# Sheet1.net
KiCad netlist of a schematic drawn in Altium Designer
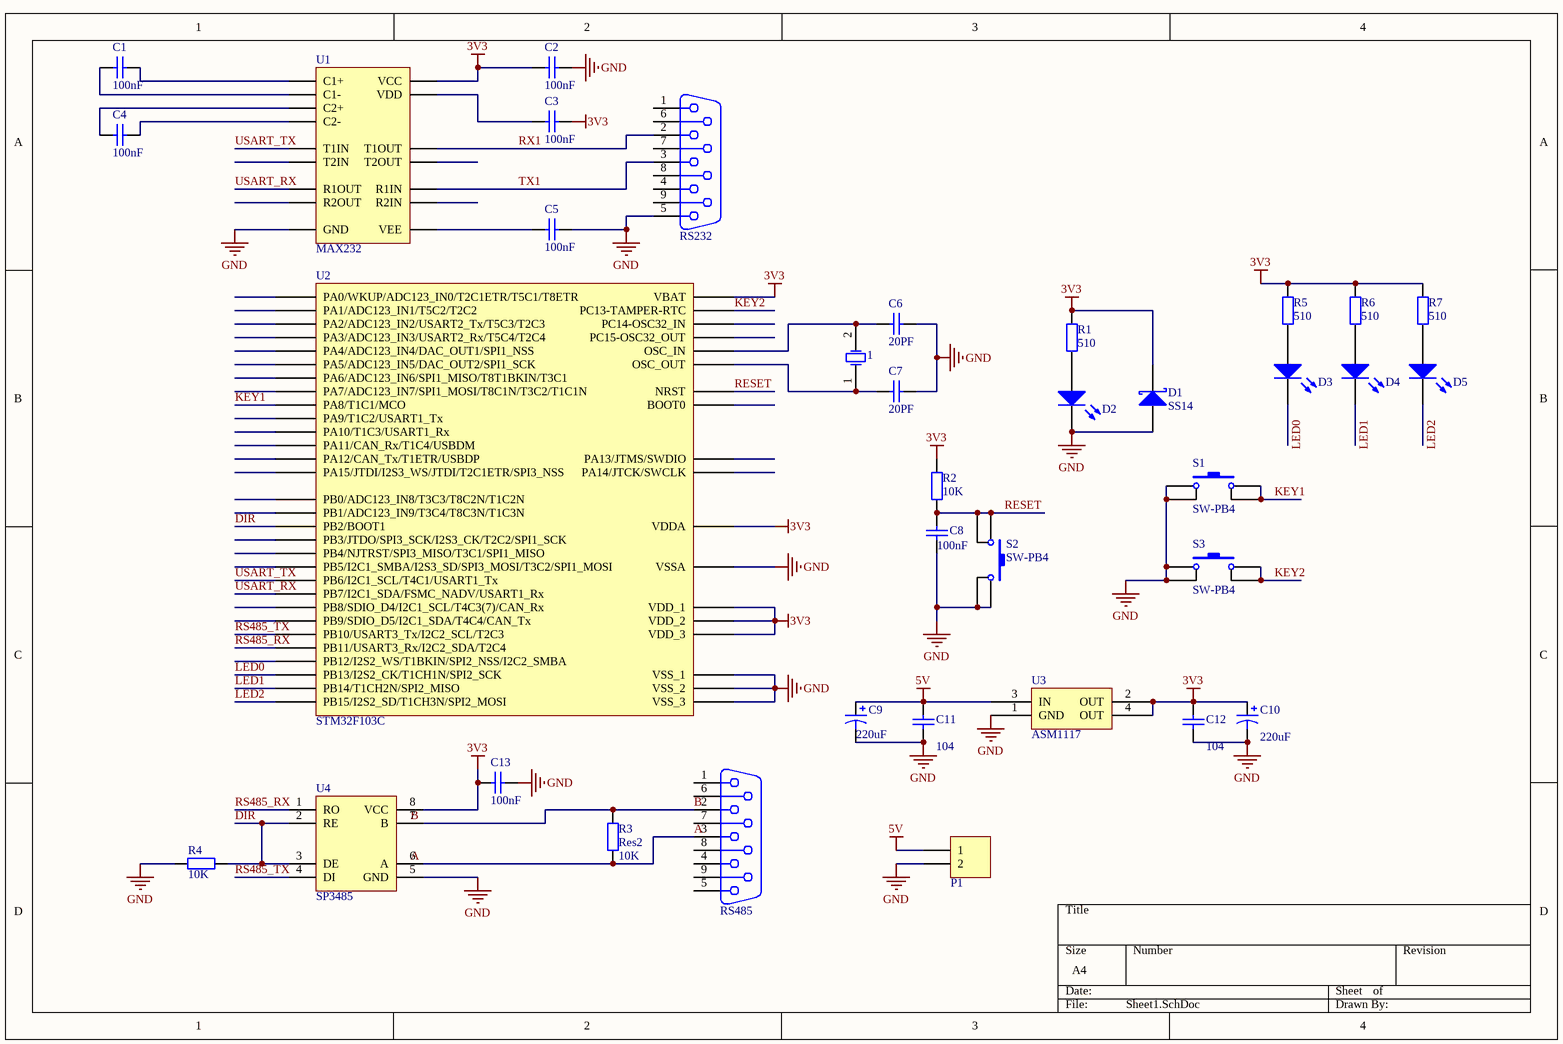
[diagram p0: Sheet1.SchDoc]

(export (version "E")
  (design (tool "Eeschema 10.0.6"))
  (components
    (comp (ref "1")
      (value "XTAL")
      (footprint "XTAL")
      (description "Crystal Oscillator")
      (fields (field (name "PUBLISHER") "Altium Limited"))
      (libsource (lib "Miscellaneous Devices") (part "XTAL"))
    )
    (comp (ref "C1")
      (value "100nF")
      (footprint "0805")
      (description "Capacitor")
      (fields (field (name "Comment") "Cap") (field (name "PUBLISHER") "Altium Limited"))
      (libsource (lib "Miscellaneous Devices") (part "Cap"))
    )
    (comp (ref "C2")
      (value "100nF")
      (footprint "0805")
      (description "Capacitor")
      (fields (field (name "Comment") "Cap") (field (name "PUBLISHER") "Altium Limited"))
      (libsource (lib "Miscellaneous Devices") (part "Cap"))
    )
    (comp (ref "C3")
      (value "100nF")
      (footprint "0805")
      (description "Capacitor")
      (fields (field (name "Comment") "Cap") (field (name "PUBLISHER") "Altium Limited"))
      (libsource (lib "Miscellaneous Devices") (part "Cap"))
    )
    (comp (ref "C4")
      (value "100nF")
      (footprint "0805")
      (description "Capacitor")
      (fields (field (name "Comment") "Cap") (field (name "PUBLISHER") "Altium Limited"))
      (libsource (lib "Miscellaneous Devices") (part "Cap"))
    )
    (comp (ref "C5")
      (value "100nF")
      (footprint "0805")
      (description "Capacitor")
      (fields (field (name "Comment") "Cap") (field (name "PUBLISHER") "Altium Limited"))
      (libsource (lib "Miscellaneous Devices") (part "Cap"))
    )
    (comp (ref "C6")
      (value "20PF")
      (footprint "0805")
      (description "Capacitor")
      (fields (field (name "PUBLISHER") "Altium Limited"))
      (libsource (lib "Miscellaneous Devices") (part "Cap"))
    )
    (comp (ref "C7")
      (value "20PF")
      (footprint "0805")
      (description "Capacitor")
      (fields (field (name "PUBLISHER") "Altium Limited"))
      (libsource (lib "Miscellaneous Devices") (part "Cap"))
    )
    (comp (ref "C8")
      (value "100nF")
      (footprint "0805")
      (description "Capacitor")
      (fields (field (name "Comment") "Cap") (field (name "PUBLISHER") "Altium Limited"))
      (libsource (lib "Miscellaneous Devices") (part "Cap"))
    )
    (comp (ref "C9")
      (value "220uF")
      (footprint "CAP-3528")
      (description "Polarized Capacitor (Radial)")
      (fields (field (name "Comment") "Cap Pol1") (field (name "PUBLISHER") "Altium Limited"))
      (libsource (lib "Miscellaneous Devices") (part "Cap Pol1"))
    )
    (comp (ref "C10")
      (value "220uF")
      (footprint "CAP-3528")
      (description "Polarized Capacitor (Radial)")
      (fields (field (name "Comment") "Cap Pol1") (field (name "PUBLISHER") "Altium Limited"))
      (libsource (lib "Miscellaneous Devices") (part "Cap Pol1"))
    )
    (comp (ref "C11")
      (value "104")
      (footprint "0805")
      (description "Capacitor")
      (fields (field (name "Comment") "Cap") (field (name "PUBLISHER") "Altium Limited"))
      (libsource (lib "Miscellaneous Devices") (part "Cap"))
    )
    (comp (ref "C12")
      (value "104")
      (footprint "0805")
      (description "Capacitor")
      (fields (field (name "Comment") "Cap") (field (name "PUBLISHER") "Altium Limited"))
      (libsource (lib "Miscellaneous Devices") (part "Cap"))
    )
    (comp (ref "C13")
      (value "100nF")
      (footprint "0805")
      (description "Capacitor")
      (fields (field (name "Comment") "Cap") (field (name "PUBLISHER") "Altium Limited"))
      (libsource (lib "Miscellaneous Devices") (part "Cap"))
    )
    (comp (ref "D1")
      (value "D-Schottky")
      (footprint "DIODE-SMA")
      (description "肖特基二极管")
      (fields (field (name "TYPE") "SS14") (field (name "PUBLISHER") "Altium Limited"))
      (libsource (lib "Fszhang") (part "D-Schottky"))
    )
    (comp (ref "D2")
      (value "LED0")
      (footprint "LED_0805")
      (description "发光二极管")
      (fields (field (name "PUBLISHER") "Altium Limited"))
      (libsource (lib "Fszhang") (part "LED0"))
    )
    (comp (ref "D3")
      (value "LED0")
      (footprint "LED_0805")
      (description "发光二极管")
      (fields (field (name "PUBLISHER") "Altium Limited"))
      (libsource (lib "Fszhang") (part "LED0"))
    )
    (comp (ref "D4")
      (value "LED0")
      (footprint "LED_0805")
      (description "发光二极管")
      (fields (field (name "PUBLISHER") "Altium Limited"))
      (libsource (lib "Fszhang") (part "LED0"))
    )
    (comp (ref "D5")
      (value "LED0")
      (footprint "LED_0805")
      (description "发光二极管")
      (fields (field (name "PUBLISHER") "Altium Limited"))
      (libsource (lib "Fszhang") (part "LED0"))
    )
    (comp (ref "P1")
      (value "Header 2")
      (footprint "HDR2X1_D1")
      (description "接插件")
      (fields (field (name "PUBLISHER") "Altium Limited"))
      (libsource (lib "Fszhang") (part "Header 2"))
    )
    (comp (ref "R1")
      (value "510")
      (footprint "0805")
      (description "Resistor")
      (fields (field (name "PUBLISHER") "Altium Limited"))
      (libsource (lib "") (part "Res2_1"))
    )
    (comp (ref "R2")
      (value "10K")
      (footprint "0805")
      (description "Resistor")
      (fields (field (name "PUBLISHER") "Altium Limited"))
      (libsource (lib "") (part "Res2_1"))
    )
    (comp (ref "R3")
      (value "Res2")
      (footprint "0805")
      (description "Resistor")
      (fields (field (name "ALTIUM_VALUE") "10K") (field (name "PUBLISHER") "Altium Limited"))
      (libsource (lib "") (part "Res2_2"))
    )
    (comp (ref "R4")
      (value "10K")
      (footprint "0805")
      (description "Resistor")
      (fields (field (name "PUBLISHER") "Altium Limited"))
      (libsource (lib "Miscellaneous Devices") (part "Res2"))
    )
    (comp (ref "R5")
      (value "510")
      (footprint "0805")
      (description "Resistor")
      (fields (field (name "PUBLISHER") "Altium Limited"))
      (libsource (lib "") (part "Res2_1"))
    )
    (comp (ref "R6")
      (value "510")
      (footprint "0805")
      (description "Resistor")
      (fields (field (name "PUBLISHER") "Altium Limited"))
      (libsource (lib "") (part "Res2_1"))
    )
    (comp (ref "R7")
      (value "510")
      (footprint "0805")
      (description "Resistor")
      (fields (field (name "PUBLISHER") "Altium Limited"))
      (libsource (lib "") (part "Res2_1"))
    )
    (comp (ref "RS232")
      (value "D Connector 9")
      (footprint "HDR3X1_D1")
      (description "串口")
      (fields (field (name "PUBLISHER") "Altium Limited"))
      (libsource (lib "Fszhang") (part "D Connector 9"))
    )
    (comp (ref "RS485")
      (value "D Connector 9")
      (footprint "HDR2X1_D1")
      (description "串口")
      (fields (field (name "PUBLISHER") "Altium Limited"))
      (libsource (lib "Fszhang") (part "D Connector 9"))
    )
    (comp (ref "S1")
      (value "SW-PB4")
      (footprint "SW_PB4_A1")
      (description "微动开关")
      (fields (field (name "PUBLISHER") "Altium Limited"))
      (libsource (lib "Fszhang") (part "SW-PB4"))
    )
    (comp (ref "S2")
      (value "SW-PB4")
      (footprint "SW_PB4_A1")
      (description "微动开关")
      (fields (field (name "PUBLISHER") "Altium Limited"))
      (libsource (lib "Fszhang") (part "SW-PB4"))
    )
    (comp (ref "S3")
      (value "SW-PB4")
      (footprint "SW_PB4_A1")
      (description "微动开关")
      (fields (field (name "PUBLISHER") "Altium Limited"))
      (libsource (lib "Fszhang") (part "SW-PB4"))
    )
    (comp (ref "U1")
      (value "MAX232")
      (footprint "NSO16_M")
      (description "+5V Powered, Multi-Channel RS-232 Driver/Receiver")
      (fields (field (name "PUBLISHER") "Altium Limited"))
      (libsource (lib "Fszhang") (part "MAX232"))
    )
    (comp (ref "U2")
      (value "STM32F103C")
      (footprint "LQFP-48_M")
      (description "STM32单片机48引脚")
      (libsource (lib "Fszhang") (part "STM32F103C"))
    )
    (comp (ref "U3")
      (value "ASM1117")
      (footprint "SOT-223")
      (description "3.3V稳压芯片")
      (libsource (lib "Fszhang") (part "ASM1117"))
    )
    (comp (ref "U4")
      (value "SP3485")
      (footprint "NSO8_N")
      (description "485总线芯片")
      (libsource (lib "Fszhang") (part "SP3485"))
    )
  )
  (nets
    (net (code "1") (name "/A") (class "Default")
      (node (ref "R3") (pin "2") (pinfunction "2_2") (pintype "passive"))
      (node (ref "RS485") (pin "3") (pinfunction "3_3") (pintype "passive"))
      (node (ref "U4") (pin "6") (pinfunction "A_6") (pintype "passive"))
    )
    (net (code "2") (name "/B") (class "Default")
      (node (ref "R3") (pin "1") (pinfunction "1_1") (pintype "passive"))
      (node (ref "RS485") (pin "2") (pinfunction "2_2") (pintype "passive"))
      (node (ref "U4") (pin "7") (pinfunction "B_7") (pintype "passive"))
    )
    (net (code "3") (name "/DIR") (class "Default")
      (node (ref "R4") (pin "2") (pinfunction "2_2") (pintype "passive"))
      (node (ref "U2") (pin "20") (pinfunction "PB2/BOOT1_20") (pintype "passive"))
      (node (ref "U4") (pin "2") (pinfunction "RE_2") (pintype "passive"))
      (node (ref "U4") (pin "3") (pinfunction "DE_3") (pintype "passive"))
    )
    (net (code "4") (name "/KEY1") (class "Default")
      (node (ref "S1") (pin "2") (pinfunction "2_2") (pintype "passive"))
      (node (ref "S1") (pin "3") (pinfunction "3_3") (pintype "passive"))
      (node (ref "U2") (pin "29") (pinfunction "PA8/T1C1/MCO_29") (pintype "passive"))
    )
    (net (code "5") (name "/KEY2") (class "Default")
      (node (ref "S3") (pin "2") (pinfunction "2_2") (pintype "passive"))
      (node (ref "S3") (pin "3") (pinfunction "3_3") (pintype "passive"))
      (node (ref "U2") (pin "2") (pinfunction "PC13-TAMPER-RTC_2") (pintype "passive"))
    )
    (net (code "6") (name "/LED0") (class "Default")
      (node (ref "D3") (pin "2") (pinfunction "K_2") (pintype "passive"))
      (node (ref "U2") (pin "26") (pinfunction "PB13/I2S2_CK/T1CH1N/SPI2_SCK_26") (pintype "passive"))
    )
    (net (code "7") (name "/LED1") (class "Default")
      (node (ref "D4") (pin "2") (pinfunction "K_2") (pintype "passive"))
      (node (ref "U2") (pin "27") (pinfunction "PB14/T1CH2N/SPI2_MISO_27") (pintype "passive"))
    )
    (net (code "8") (name "/LED2") (class "Default")
      (node (ref "D5") (pin "2") (pinfunction "K_2") (pintype "passive"))
      (node (ref "U2") (pin "28") (pinfunction "PB15/I2S2_SD/T1CH3N/SPI2_MOSI_28") (pintype "passive"))
    )
    (net (code "9") (name "/RESET") (class "Default")
      (node (ref "C8") (pin "1") (pinfunction "1_1") (pintype "passive"))
      (node (ref "R2") (pin "1") (pinfunction "1_1") (pintype "passive"))
      (node (ref "S2") (pin "1") (pinfunction "1_1") (pintype "passive"))
      (node (ref "S2") (pin "4") (pinfunction "4_4") (pintype "passive"))
      (node (ref "U2") (pin "7") (pinfunction "NRST_7") (pintype "passive"))
    )
    (net (code "10") (name "/RS485_RX") (class "Default")
      (node (ref "U2") (pin "22") (pinfunction "PB11/USART3_Rx/I2C2_SDA/T2C4_22") (pintype "passive"))
      (node (ref "U4") (pin "1") (pinfunction "RO_1") (pintype "passive"))
    )
    (net (code "11") (name "/RS485_TX") (class "Default")
      (node (ref "U2") (pin "21") (pinfunction "PB10/USART3_Tx/I2C2_SCL/T2C3_21") (pintype "passive"))
      (node (ref "U4") (pin "4") (pinfunction "DI_4") (pintype "passive"))
    )
    (net (code "12") (name "/RX1") (class "Default")
      (node (ref "RS232") (pin "2") (pinfunction "2_2") (pintype "passive"))
      (node (ref "U1") (pin "14") (pinfunction "T1OUT_14") (pintype "passive"))
    )
    (net (code "13") (name "/TX1") (class "Default")
      (node (ref "RS232") (pin "3") (pinfunction "3_3") (pintype "passive"))
      (node (ref "U1") (pin "13") (pinfunction "R1IN_13") (pintype "passive"))
    )
    (net (code "14") (name "/USART_RX") (class "Default")
      (node (ref "U1") (pin "12") (pinfunction "R1OUT_12") (pintype "passive"))
      (node (ref "U2") (pin "43") (pinfunction "PB7/I2C1_SDA/FSMC_NADV/USART1_Rx_43") (pintype "passive"))
    )
    (net (code "15") (name "/USART_TX") (class "Default")
      (node (ref "U1") (pin "11") (pinfunction "T1IN_11") (pintype "passive"))
      (node (ref "U2") (pin "42") (pinfunction "PB6/I2C1_SCL/T4C1/USART1_Tx_42") (pintype "passive"))
    )
    (net (code "16") (name "3V3") (class "Default")
      (node (ref "C10") (pin "1") (pinfunction "1_1") (pintype "passive"))
      (node (ref "C12") (pin "2") (pinfunction "2_2") (pintype "passive"))
      (node (ref "C13") (pin "2") (pinfunction "2_2") (pintype "passive"))
      (node (ref "C2") (pin "1") (pinfunction "1_1") (pintype "passive"))
      (node (ref "C3") (pin "2") (pinfunction "2_2") (pintype "passive"))
      (node (ref "D1") (pin "2") (pinfunction "K_2") (pintype "passive"))
      (node (ref "R1") (pin "2") (pinfunction "2_2") (pintype "passive"))
      (node (ref "R2") (pin "2") (pinfunction "2_2") (pintype "passive"))
      (node (ref "R5") (pin "2") (pinfunction "2_2") (pintype "passive"))
      (node (ref "R6") (pin "2") (pinfunction "2_2") (pintype "passive"))
      (node (ref "R7") (pin "2") (pinfunction "2_2") (pintype "passive"))
      (node (ref "U1") (pin "16") (pinfunction "VCC_16") (pintype "power_in"))
      (node (ref "U2") (pin "1") (pinfunction "VBAT_1") (pintype "passive"))
      (node (ref "U2") (pin "24") (pinfunction "VDD_1_24") (pintype "passive"))
      (node (ref "U2") (pin "36") (pinfunction "VDD_2_36") (pintype "passive"))
      (node (ref "U2") (pin "48") (pinfunction "VDD_3_48") (pintype "passive"))
      (node (ref "U2") (pin "9") (pinfunction "VDDA_9") (pintype "passive"))
      (node (ref "U3") (pin "2") (pinfunction "OUT_2") (pintype "passive"))
      (node (ref "U3") (pin "4") (pinfunction "OUT_4") (pintype "passive"))
      (node (ref "U4") (pin "8") (pinfunction "VCC_8") (pintype "passive"))
    )
    (net (code "17") (name "5V") (class "Default")
      (node (ref "C11") (pin "2") (pinfunction "2_2") (pintype "passive"))
      (node (ref "C9") (pin "1") (pinfunction "1_1") (pintype "passive"))
      (node (ref "P1") (pin "1") (pinfunction "1_1") (pintype "passive"))
      (node (ref "U3") (pin "3") (pinfunction "IN_3") (pintype "passive"))
    )
    (net (code "18") (name "GND") (class "Default")
      (node (ref "C10") (pin "2") (pinfunction "2_2") (pintype "passive"))
      (node (ref "C11") (pin "1") (pinfunction "1_1") (pintype "passive"))
      (node (ref "C12") (pin "1") (pinfunction "1_1") (pintype "passive"))
      (node (ref "C13") (pin "1") (pinfunction "1_1") (pintype "passive"))
      (node (ref "C2") (pin "2") (pinfunction "2_2") (pintype "passive"))
      (node (ref "C5") (pin "2") (pinfunction "2_2") (pintype "passive"))
      (node (ref "C6") (pin "2") (pinfunction "2_2") (pintype "passive"))
      (node (ref "C7") (pin "2") (pinfunction "2_2") (pintype "passive"))
      (node (ref "C8") (pin "2") (pinfunction "2_2") (pintype "passive"))
      (node (ref "C9") (pin "2") (pinfunction "2_2") (pintype "passive"))
      (node (ref "D1") (pin "1") (pinfunction "A_1") (pintype "passive"))
      (node (ref "D2") (pin "2") (pinfunction "K_2") (pintype "passive"))
      (node (ref "P1") (pin "2") (pinfunction "2_2") (pintype "passive"))
      (node (ref "R4") (pin "1") (pinfunction "1_1") (pintype "passive"))
      (node (ref "RS232") (pin "5") (pinfunction "5_5") (pintype "passive"))
      (node (ref "S1") (pin "1") (pinfunction "1_1") (pintype "passive"))
      (node (ref "S1") (pin "4") (pinfunction "4_4") (pintype "passive"))
      (node (ref "S2") (pin "2") (pinfunction "2_2") (pintype "passive"))
      (node (ref "S2") (pin "3") (pinfunction "3_3") (pintype "passive"))
      (node (ref "S3") (pin "1") (pinfunction "1_1") (pintype "passive"))
      (node (ref "S3") (pin "4") (pinfunction "4_4") (pintype "passive"))
      (node (ref "U1") (pin "15") (pinfunction "GND_15") (pintype "power_in"))
      (node (ref "U2") (pin "23") (pinfunction "VSS_1_23") (pintype "passive"))
      (node (ref "U2") (pin "35") (pinfunction "VSS_2_35") (pintype "passive"))
      (node (ref "U2") (pin "47") (pinfunction "VSS_3_47") (pintype "passive"))
      (node (ref "U2") (pin "8") (pinfunction "VSSA_8") (pintype "passive"))
      (node (ref "U3") (pin "1") (pinfunction "GND_1") (pintype "passive"))
      (node (ref "U4") (pin "5") (pinfunction "GND_5") (pintype "passive"))
    )
    (net (code "19") (name "Net-(1-OSC1)") (class "Default")
      (node (ref "1") (pin "1") (pinfunction "OSC1_1") (pintype "passive"))
      (node (ref "C7") (pin "1") (pinfunction "1_1") (pintype "passive"))
      (node (ref "U2") (pin "6") (pinfunction "OSC_OUT_6") (pintype "passive"))
    )
    (net (code "20") (name "Net-(1-OSC2)") (class "Default")
      (node (ref "1") (pin "2") (pinfunction "OSC2_2") (pintype "passive"))
      (node (ref "C6") (pin "1") (pinfunction "1_1") (pintype "passive"))
      (node (ref "U2") (pin "5") (pinfunction "OSC_IN_5") (pintype "passive"))
    )
    (net (code "21") (name "Net-(D2-A)") (class "Default")
      (node (ref "D2") (pin "1") (pinfunction "A_1") (pintype "passive"))
      (node (ref "R1") (pin "1") (pinfunction "1_1") (pintype "passive"))
    )
    (net (code "22") (name "Net-(D3-A)") (class "Default")
      (node (ref "D3") (pin "1") (pinfunction "A_1") (pintype "passive"))
      (node (ref "R5") (pin "1") (pinfunction "1_1") (pintype "passive"))
    )
    (net (code "23") (name "Net-(D4-A)") (class "Default")
      (node (ref "D4") (pin "1") (pinfunction "A_1") (pintype "passive"))
      (node (ref "R6") (pin "1") (pinfunction "1_1") (pintype "passive"))
    )
    (net (code "24") (name "Net-(D5-A)") (class "Default")
      (node (ref "D5") (pin "1") (pinfunction "A_1") (pintype "passive"))
      (node (ref "R7") (pin "1") (pinfunction "1_1") (pintype "passive"))
    )
    (net (code "25") (name "Net-(U1-C1+)") (class "Default")
      (node (ref "C1") (pin "1") (pinfunction "1_1") (pintype "passive"))
      (node (ref "U1") (pin "1") (pinfunction "C1+_1") (pintype "passive"))
    )
    (net (code "26") (name "Net-(U1-C1-)") (class "Default")
      (node (ref "C1") (pin "2") (pinfunction "2_2") (pintype "passive"))
      (node (ref "U1") (pin "3") (pinfunction "C1-_3") (pintype "passive"))
    )
    (net (code "27") (name "Net-(U1-C2+)") (class "Default")
      (node (ref "C4") (pin "2") (pinfunction "2_2") (pintype "passive"))
      (node (ref "U1") (pin "4") (pinfunction "C2+_4") (pintype "passive"))
    )
    (net (code "28") (name "Net-(U1-C2-)") (class "Default")
      (node (ref "C4") (pin "1") (pinfunction "1_1") (pintype "passive"))
      (node (ref "U1") (pin "5") (pinfunction "C2-_5") (pintype "passive"))
    )
    (net (code "29") (name "Net-(U1-VDD)") (class "Default")
      (node (ref "C3") (pin "1") (pinfunction "1_1") (pintype "passive"))
      (node (ref "U1") (pin "2") (pinfunction "VDD_2") (pintype "power_in"))
    )
    (net (code "30") (name "Net-(U1-VEE)") (class "Default")
      (node (ref "C5") (pin "1") (pinfunction "1_1") (pintype "passive"))
      (node (ref "U1") (pin "6") (pinfunction "VEE_6") (pintype "power_in"))
    )
    (net (code "31") (name "unconnected-(RS232-MH1-Pad10)") (class "Default")
      (node (ref "RS232") (pin "10") (pinfunction "MH1_10") (pintype "passive"))
    )
    (net (code "32") (name "unconnected-(RS232-MH2-Pad11)") (class "Default")
      (node (ref "RS232") (pin "11") (pinfunction "MH2_11") (pintype "passive"))
    )
    (net (code "33") (name "unconnected-(RS232-Pad1)") (class "Default")
      (node (ref "RS232") (pin "1") (pinfunction "1_1") (pintype "passive"))
    )
    (net (code "34") (name "unconnected-(RS232-Pad4)") (class "Default")
      (node (ref "RS232") (pin "4") (pinfunction "4_4") (pintype "passive"))
    )
    (net (code "35") (name "unconnected-(RS232-Pad6)") (class "Default")
      (node (ref "RS232") (pin "6") (pinfunction "6_6") (pintype "passive"))
    )
    (net (code "36") (name "unconnected-(RS232-Pad7)") (class "Default")
      (node (ref "RS232") (pin "7") (pinfunction "7_7") (pintype "passive"))
    )
    (net (code "37") (name "unconnected-(RS232-Pad8)") (class "Default")
      (node (ref "RS232") (pin "8") (pinfunction "8_8") (pintype "passive"))
    )
    (net (code "38") (name "unconnected-(RS232-Pad9)") (class "Default")
      (node (ref "RS232") (pin "9") (pinfunction "9_9") (pintype "passive"))
    )
    (net (code "39") (name "unconnected-(RS485-MH1-Pad10)") (class "Default")
      (node (ref "RS485") (pin "10") (pinfunction "MH1_10") (pintype "passive"))
    )
    (net (code "40") (name "unconnected-(RS485-MH2-Pad11)") (class "Default")
      (node (ref "RS485") (pin "11") (pinfunction "MH2_11") (pintype "passive"))
    )
    (net (code "41") (name "unconnected-(RS485-Pad1)") (class "Default")
      (node (ref "RS485") (pin "1") (pinfunction "1_1") (pintype "passive"))
    )
    (net (code "42") (name "unconnected-(RS485-Pad4)") (class "Default")
      (node (ref "RS485") (pin "4") (pinfunction "4_4") (pintype "passive"))
    )
    (net (code "43") (name "unconnected-(RS485-Pad5)") (class "Default")
      (node (ref "RS485") (pin "5") (pinfunction "5_5") (pintype "passive"))
    )
    (net (code "44") (name "unconnected-(RS485-Pad6)") (class "Default")
      (node (ref "RS485") (pin "6") (pinfunction "6_6") (pintype "passive"))
    )
    (net (code "45") (name "unconnected-(RS485-Pad7)") (class "Default")
      (node (ref "RS485") (pin "7") (pinfunction "7_7") (pintype "passive"))
    )
    (net (code "46") (name "unconnected-(RS485-Pad8)") (class "Default")
      (node (ref "RS485") (pin "8") (pinfunction "8_8") (pintype "passive"))
    )
    (net (code "47") (name "unconnected-(RS485-Pad9)") (class "Default")
      (node (ref "RS485") (pin "9") (pinfunction "9_9") (pintype "passive"))
    )
    (net (code "48") (name "unconnected-(U1-R2IN-Pad8)") (class "Default")
      (node (ref "U1") (pin "8") (pinfunction "R2IN_8") (pintype "passive"))
    )
    (net (code "49") (name "unconnected-(U1-R2OUT-Pad9)") (class "Default")
      (node (ref "U1") (pin "9") (pinfunction "R2OUT_9") (pintype "passive"))
    )
    (net (code "50") (name "unconnected-(U1-T2IN-Pad10)") (class "Default")
      (node (ref "U1") (pin "10") (pinfunction "T2IN_10") (pintype "passive"))
    )
    (net (code "51") (name "unconnected-(U1-T2OUT-Pad7)") (class "Default")
      (node (ref "U1") (pin "7") (pinfunction "T2OUT_7") (pintype "passive"))
    )
    (net (code "52") (name "unconnected-(U2-BOOT0-Pad44)") (class "Default")
      (node (ref "U2") (pin "44") (pinfunction "BOOT0_44") (pintype "passive"))
    )
    (net (code "53") (name "unconnected-(U2-PA0{slash}WKUP{slash}ADC123_IN0{slash}T2C1ETR{slash}T5C1{slash}T8ETR-Pad10)") (class "Default")
      (node (ref "U2") (pin "10") (pinfunction "PA0/WKUP/ADC123_IN0/T2C1ETR/T5C1/T8ETR_10") (pintype "passive"))
    )
    (net (code "54") (name "unconnected-(U2-PA1{slash}ADC123_IN1{slash}T5C2{slash}T2C2-Pad11)") (class "Default")
      (node (ref "U2") (pin "11") (pinfunction "PA1/ADC123_IN1/T5C2/T2C2_11") (pintype "passive"))
    )
    (net (code "55") (name "unconnected-(U2-PA2{slash}ADC123_IN2{slash}USART2_Tx{slash}T5C3{slash}T2C3-Pad12)") (class "Default")
      (node (ref "U2") (pin "12") (pinfunction "PA2/ADC123_IN2/USART2_Tx/T5C3/T2C3_12") (pintype "passive"))
    )
    (net (code "56") (name "unconnected-(U2-PA3{slash}ADC123_IN3{slash}USART2_Rx{slash}T5C4{slash}T2C4-Pad13)") (class "Default")
      (node (ref "U2") (pin "13") (pinfunction "PA3/ADC123_IN3/USART2_Rx/T5C4/T2C4_13") (pintype "passive"))
    )
    (net (code "57") (name "unconnected-(U2-PA4{slash}ADC123_IN4{slash}DAC_OUT1{slash}SPI1_NSS-Pad14)") (class "Default")
      (node (ref "U2") (pin "14") (pinfunction "PA4/ADC123_IN4/DAC_OUT1/SPI1_NSS_14") (pintype "passive"))
    )
    (net (code "58") (name "unconnected-(U2-PA5{slash}ADC123_IN5{slash}DAC_OUT2{slash}SPI1_SCK-Pad15)") (class "Default")
      (node (ref "U2") (pin "15") (pinfunction "PA5/ADC123_IN5/DAC_OUT2/SPI1_SCK_15") (pintype "passive"))
    )
    (net (code "59") (name "unconnected-(U2-PA6{slash}ADC123_IN6{slash}SPI1_MISO{slash}T8T1BKIN{slash}T3C1-Pad16)") (class "Default")
      (node (ref "U2") (pin "16") (pinfunction "PA6/ADC123_IN6/SPI1_MISO/T8T1BKIN/T3C1_16") (pintype "passive"))
    )
    (net (code "60") (name "unconnected-(U2-PA7{slash}ADC123_IN7{slash}SPI1_MOSI{slash}T8C1N{slash}T3C2{slash}T1C1N-Pad17)") (class "Default")
      (node (ref "U2") (pin "17") (pinfunction "PA7/ADC123_IN7/SPI1_MOSI/T8C1N/T3C2/T1C1N_17") (pintype "passive"))
    )
    (net (code "61") (name "unconnected-(U2-PA9{slash}T1C2{slash}USART1_Tx-Pad30)") (class "Default")
      (node (ref "U2") (pin "30") (pinfunction "PA9/T1C2/USART1_Tx_30") (pintype "passive"))
    )
    (net (code "62") (name "unconnected-(U2-PA10{slash}T1C3{slash}USART1_Rx-Pad31)") (class "Default")
      (node (ref "U2") (pin "31") (pinfunction "PA10/T1C3/USART1_Rx_31") (pintype "passive"))
    )
    (net (code "63") (name "unconnected-(U2-PA11{slash}CAN_Rx{slash}T1C4{slash}USBDM-Pad32)") (class "Default")
      (node (ref "U2") (pin "32") (pinfunction "PA11/CAN_Rx/T1C4/USBDM_32") (pintype "passive"))
    )
    (net (code "64") (name "unconnected-(U2-PA12{slash}CAN_Tx{slash}T1ETR{slash}USBDP-Pad33)") (class "Default")
      (node (ref "U2") (pin "33") (pinfunction "PA12/CAN_Tx/T1ETR/USBDP_33") (pintype "passive"))
    )
    (net (code "65") (name "unconnected-(U2-PA13{slash}JTMS{slash}SWDIO-Pad34)") (class "Default")
      (node (ref "U2") (pin "34") (pinfunction "PA13/JTMS/SWDIO_34") (pintype "passive"))
    )
    (net (code "66") (name "unconnected-(U2-PA14{slash}JTCK{slash}SWCLK-Pad37)") (class "Default")
      (node (ref "U2") (pin "37") (pinfunction "PA14/JTCK/SWCLK_37") (pintype "passive"))
    )
    (net (code "67") (name "unconnected-(U2-PA15{slash}JTDI{slash}I2S3_WS{slash}JTDI{slash}T2C1ETR{slash}SPI3_NSS-Pad38)") (class "Default")
      (node (ref "U2") (pin "38") (pinfunction "PA15/JTDI/I2S3_WS/JTDI/T2C1ETR/SPI3_NSS_38") (pintype "passive"))
    )
    (net (code "68") (name "unconnected-(U2-PB0{slash}ADC123_IN8{slash}T3C3{slash}T8C2N{slash}T1C2N-Pad18)") (class "Default")
      (node (ref "U2") (pin "18") (pinfunction "PB0/ADC123_IN8/T3C3/T8C2N/T1C2N_18") (pintype "passive"))
    )
    (net (code "69") (name "unconnected-(U2-PB1{slash}ADC123_IN9{slash}T3C4{slash}T8C3N{slash}T1C3N-Pad19)") (class "Default")
      (node (ref "U2") (pin "19") (pinfunction "PB1/ADC123_IN9/T3C4/T8C3N/T1C3N_19") (pintype "passive"))
    )
    (net (code "70") (name "unconnected-(U2-PB3{slash}JTDO{slash}SPI3_SCK{slash}I2S3_CK{slash}T2C2{slash}SPI1_SCK-Pad39)") (class "Default")
      (node (ref "U2") (pin "39") (pinfunction "PB3/JTDO/SPI3_SCK/I2S3_CK/T2C2/SPI1_SCK_39") (pintype "passive"))
    )
    (net (code "71") (name "unconnected-(U2-PB4{slash}NJTRST{slash}SPI3_MISO{slash}T3C1{slash}SPI1_MISO-Pad40)") (class "Default")
      (node (ref "U2") (pin "40") (pinfunction "PB4/NJTRST/SPI3_MISO/T3C1/SPI1_MISO_40") (pintype "passive"))
    )
    (net (code "72") (name "unconnected-(U2-PB5{slash}I2C1_SMBA{slash}I2S3_SD{slash}SPI3_MOSI{slash}T3C2{slash}SPI1_MOSI-Pad41)") (class "Default")
      (node (ref "U2") (pin "41") (pinfunction "PB5/I2C1_SMBA/I2S3_SD/SPI3_MOSI/T3C2/SPI1_MOSI_41") (pintype "passive"))
    )
    (net (code "73") (name "unconnected-(U2-PB8{slash}SDIO_D4{slash}I2C1_SCL{slash}T4C3(7){slash}CAN_Rx-Pad45)") (class "Default")
      (node (ref "U2") (pin "45") (pinfunction "PB8/SDIO_D4/I2C1_SCL/T4C3(7)/CAN_Rx_45") (pintype "passive"))
    )
    (net (code "74") (name "unconnected-(U2-PB9{slash}SDIO_D5{slash}I2C1_SDA{slash}T4C4{slash}CAN_Tx-Pad46)") (class "Default")
      (node (ref "U2") (pin "46") (pinfunction "PB9/SDIO_D5/I2C1_SDA/T4C4/CAN_Tx_46") (pintype "passive"))
    )
    (net (code "75") (name "unconnected-(U2-PB12{slash}I2S2_WS{slash}T1BKIN{slash}SPI2_NSS{slash}I2C2_SMBA-Pad25)") (class "Default")
      (node (ref "U2") (pin "25") (pinfunction "PB12/I2S2_WS/T1BKIN/SPI2_NSS/I2C2_SMBA_25") (pintype "passive"))
    )
    (net (code "76") (name "unconnected-(U2-PC14-OSC32_IN-Pad3)") (class "Default")
      (node (ref "U2") (pin "3") (pinfunction "PC14-OSC32_IN_3") (pintype "passive"))
    )
    (net (code "77") (name "unconnected-(U2-PC15-OSC32_OUT-Pad4)") (class "Default")
      (node (ref "U2") (pin "4") (pinfunction "PC15-OSC32_OUT_4") (pintype "passive"))
    )
  )
)
